# ID1.net
KiCad netlist of a schematic drawn in Altium Designer
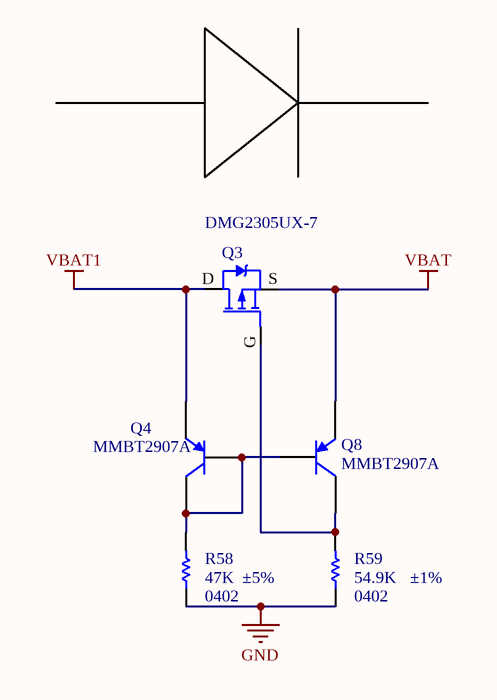
[diagram p0: ID1.SchDoc]

(export (version "E")
  (design (tool "Eeschema 10.0.6"))
  (components
    (comp (ref "Q3")
      (value "DMG2305UX")
      (footprint "DMG2305UX-7")
      (description "MOSFET P-CH 20V 4.2A SOT23")
      (fields
        (field (name "MANUFACTURER") "Diodes Incorporated")
        (field (name "MANUFACTURER PART NUMBER") "DMG2305UX-7")
        (field (name "CREATOR") "osman")
      )
      (libsource (lib "OLogic-Trans-Drivers") (part "DMG2305UX"))
    )
    (comp (ref "Q4")
      (value "MMBT2907A")
      (footprint "SOT23")
      (description "PNP General Purpose Amplifier")
      (fields (field (name "MANUFACTURER") "Fairchild Semiconductor"))
      (libsource (lib "OLogic-Trans-Drivers") (part "MMBT2907A"))
    )
    (comp (ref "Q8")
      (value "MMBT2907A")
      (footprint "SOT23")
      (description "PNP General Purpose Amplifier")
      (fields (field (name "MANUFACTURER") "Fairchild Semiconductor"))
      (libsource (lib "OLogic-Trans-Drivers") (part "MMBT2907A"))
    )
    (comp (ref "R58")
      (value "47K")
      (footprint "RESC0402(1005)_N")
      (description "47K 0402")
      (fields
        (field (name "MANUFACTURER") "Panasonic Electronic Components")
        (field (name "MANUFACTURER PART NUMBER") "ERJ-2GEJ473X")
        (field (name "TOLERANCE") "±5%")
        (field (name "SUPPLIER DEVICE PACKAGE") "0402")
      )
      (libsource (lib "OLogic-Passive") (part "RES 47K OHM 5% 1/10W 0402"))
    )
    (comp (ref "R59")
      (value "54.9K")
      (footprint "RESC0402(1005)_N")
      (description "54.9K 1% 0402")
      (fields
        (field (name "MANUFACTURER") "Panasonic Electronic Components")
        (field (name "MANUFACTURER PART NUMBER") "ERJ-2RKF5492X")
        (field (name "TOLERANCE") "±1%")
        (field (name "SUPPLIER DEVICE PACKAGE") "0402")
      )
      (libsource (lib "OLogic-Passive") (part "RES 54.9K OHM 1% 1/10W 0402"))
    )
  )
  (nets
    (net (code "1") (name "GND") (class "Default")
      (node (ref "R58") (pin "1") (pinfunction "1_1") (pintype "passive"))
      (node (ref "R59") (pin "1") (pinfunction "1_1") (pintype "passive"))
    )
    (net (code "2") (name "Net-(Q4-B)") (class "Default")
      (node (ref "Q4") (pin "1") (pinfunction "B_1") (pintype "passive"))
      (node (ref "Q4") (pin "3") (pinfunction "C_3") (pintype "passive"))
      (node (ref "Q8") (pin "1") (pinfunction "B_1") (pintype "passive"))
      (node (ref "R58") (pin "2") (pinfunction "2_2") (pintype "passive"))
    )
    (net (code "3") (name "Net-(Q8-C)") (class "Default")
      (node (ref "Q3") (pin "G") (pinfunction "G_G") (pintype "passive"))
      (node (ref "Q8") (pin "3") (pinfunction "C_3") (pintype "passive"))
      (node (ref "R59") (pin "2") (pinfunction "2_2") (pintype "passive"))
    )
    (net (code "4") (name "VBAT") (class "Default")
      (node (ref "Q3") (pin "S") (pinfunction "S_S") (pintype "passive"))
      (node (ref "Q8") (pin "2") (pinfunction "E_2") (pintype "passive"))
    )
    (net (code "5") (name "VBAT1") (class "Default")
      (node (ref "Q3") (pin "D") (pinfunction "D_D") (pintype "passive"))
      (node (ref "Q4") (pin "2") (pinfunction "E_2") (pintype "passive"))
    )
  )
)
